# Battery_Power.net
KiCad netlist of a schematic drawn in Altium Designer
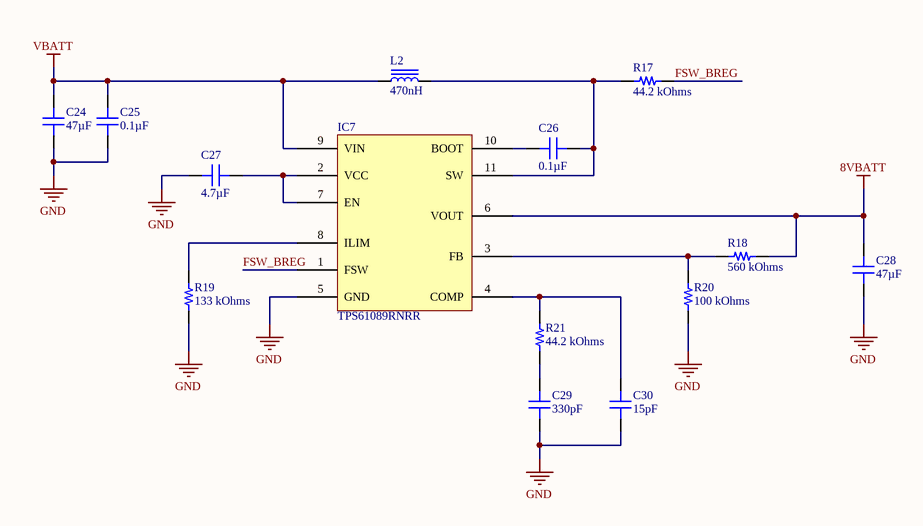
[diagram p0: Battery Power.SchDoc]

(export (version "E")
  (design (tool "Eeschema 10.0.6"))
  (components
    (comp (ref "C24")
      (value "47µF")
      (footprint "CAP 1210_3225 - 2.8MM")
      (description "CAP CER 47UF 10V X7R 1210")
      (fields (field (name "PART NUMBER") "LMK325B7476MM-PR") (field (name "MANUFACTURER") "Taiyo Yuden"))
      (libsource (lib "Celestial Altium Library - altium_library") (part "Capacitor"))
    )
    (comp (ref "C25")
      (value "0.1µF")
      (footprint "CAP 0201_0603")
      (description "CAP CER 0.1UF 16V X5R 0201")
      (fields
        (field (name "PART NUMBER") "GRM033R61C104ME84D")
        (field (name "MANUFACTURER") "Murata Electronics")
      )
      (libsource (lib "Celestial Altium Library - altium_library") (part "Capacitor"))
    )
    (comp (ref "C26")
      (value "0.1µF")
      (footprint "CAP 0201_0603")
      (description "CAP CER 0.1UF 16V X5R 0201")
      (fields
        (field (name "PART NUMBER") "GRM033R61C104ME84D")
        (field (name "MANUFACTURER") "Murata Electronics")
      )
      (libsource (lib "Celestial Altium Library - altium_library") (part "Capacitor"))
    )
    (comp (ref "C27")
      (value "4.7µF")
      (footprint "CAP 0402_1005")
      (description "CAP CER 4.7UF 10V X5R 0402")
      (fields
        (field (name "PART NUMBER") "CL05A475KP5NRNC")
        (field (name "MANUFACTURER") "Samsung Electro-Mechanics")
      )
      (libsource (lib "Celestial Altium Library - altium_library") (part "Capacitor"))
    )
    (comp (ref "C28")
      (value "47µF")
      (footprint "CAP 1210_3225 - 2.8MM")
      (description "CAP CER 47UF 16V X5R 1210")
      (fields (field (name "PART NUMBER") "C1210C476M4PACTU") (field (name "MANUFACTURER") "KEMET"))
      (libsource (lib "Celestial Altium Library - altium_library") (part "Capacitor"))
    )
    (comp (ref "C29")
      (value "330pF")
      (footprint "CAP 0201_0603")
      (description "CAP CER 330PF 25V X7R 0201")
      (fields
        (field (name "PART NUMBER") "CL03B331KA3NNNC")
        (field (name "MANUFACTURER") "Samsung Electro-Mechanics")
      )
      (libsource (lib "Celestial Altium Library - altium_library") (part "Capacitor"))
    )
    (comp (ref "C30")
      (value "15pF")
      (footprint "CAP 0201_0603")
      (description "CAP CER 15PF 25V C0G 0201")
      (fields
        (field (name "PART NUMBER") "CGA1A2C0G1E150J030BA")
        (field (name "MANUFACTURER") "TDK Corporation")
      )
      (libsource (lib "Celestial Altium Library - altium_library") (part "Capacitor"))
    )
    (comp (ref "IC7")
      (value "TPS61089RNRR")
      (footprint "TI VQFN-11 2.5x2.1 RNR")
      (description "IC REG BOOST ADJ 7A 11VQFN")
      (fields (field (name "MANUFACTURER") "Texas Instruments"))
      (libsource (lib "Celestial Altium Library - altium_library") (part "TI TPS61089"))
    )
    (comp (ref "L2")
      (value "470nH")
      (footprint "BOURNS SRP5030T")
      (description "FIXED IND 470NH 12A 7.4 MOHM SMD")
      (fields (field (name "PART NUMBER") "SRP5030T-R47M") (field (name "MANUFACTURER") "Bourns Inc."))
      (libsource (lib "Celestial Altium Library - altium_library") (part "Inductor"))
    )
    (comp (ref "R17")
      (value "44.2 kOhms")
      (footprint "RES 0201_0603")
      (description "RES SMD 44.2K OHM 1% 1/20W 0201")
      (fields
        (field (name "PART NUMBER") "ERJ-1GNF4422C")
        (field (name "MANUFACTURER") "Panasonic Electronic Components")
      )
      (libsource (lib "Celestial Altium Library - altium_library") (part "Resistor"))
    )
    (comp (ref "R18")
      (value "560 kOhms")
      (footprint "RES 0201_0603")
      (description "RES SMD 560K OHM 1% 1/20W 0201")
      (fields
        (field (name "PART NUMBER") "ERJ-1GNF5603C")
        (field (name "MANUFACTURER") "Panasonic Electronic Components")
      )
      (libsource (lib "Celestial Altium Library - altium_library") (part "Resistor"))
    )
    (comp (ref "R19")
      (value "133 kOhms")
      (footprint "RES 0201_0603")
      (description "RES SMD 133K OHM 1% 1/20W 0201")
      (fields
        (field (name "PART NUMBER") "ERJ-1GNF1333C")
        (field (name "MANUFACTURER") "Panasonic Electronic Components")
      )
      (libsource (lib "Celestial Altium Library - altium_library") (part "Resistor"))
    )
    (comp (ref "R20")
      (value "100 kOhms")
      (footprint "RES 0201_0603")
      (description "RES SMD 100K OHM 1% 1/20W 0201")
      (fields
        (field (name "PART NUMBER") "ERJ-1GNF1003C")
        (field (name "MANUFACTURER") "Panasonic Electronic Components")
      )
      (libsource (lib "Celestial Altium Library - altium_library") (part "Resistor"))
    )
    (comp (ref "R21")
      (value "44.2 kOhms")
      (footprint "RES 0201_0603")
      (description "RES SMD 44.2K OHM 1% 1/20W 0201")
      (fields
        (field (name "PART NUMBER") "ERJ-1GNF4422C")
        (field (name "MANUFACTURER") "Panasonic Electronic Components")
      )
      (libsource (lib "Celestial Altium Library - altium_library") (part "Resistor"))
    )
  )
  (nets
    (net (code "1") (name "/FSW_BREG") (class "Default")
      (node (ref "IC7") (pin "1") (pinfunction "FSW_1") (pintype "passive"))
      (node (ref "R17") (pin "2") (pinfunction "2_2") (pintype "passive"))
    )
    (net (code "2") (name "8VBATT") (class "Default")
      (node (ref "C28") (pin "2") (pinfunction "2_2") (pintype "passive"))
      (node (ref "IC7") (pin "6") (pinfunction "VOUT_6") (pintype "passive"))
      (node (ref "R18") (pin "1") (pinfunction "1_1") (pintype "passive"))
    )
    (net (code "3") (name "GND") (class "Default")
      (node (ref "C24") (pin "1") (pinfunction "1_1") (pintype "passive"))
      (node (ref "C25") (pin "1") (pinfunction "1_1") (pintype "passive"))
      (node (ref "C27") (pin "1") (pinfunction "1_1") (pintype "passive"))
      (node (ref "C28") (pin "1") (pinfunction "1_1") (pintype "passive"))
      (node (ref "C29") (pin "1") (pinfunction "1_1") (pintype "passive"))
      (node (ref "C30") (pin "1") (pinfunction "1_1") (pintype "passive"))
      (node (ref "IC7") (pin "5") (pinfunction "GND_5") (pintype "passive"))
      (node (ref "R19") (pin "1") (pinfunction "1_1") (pintype "passive"))
      (node (ref "R20") (pin "1") (pinfunction "1_1") (pintype "passive"))
    )
    (net (code "4") (name "Net-(C29-Pad2)") (class "Default")
      (node (ref "C29") (pin "2") (pinfunction "2_2") (pintype "passive"))
      (node (ref "R21") (pin "1") (pinfunction "1_1") (pintype "passive"))
    )
    (net (code "5") (name "Net-(IC7-BOOT)") (class "Default")
      (node (ref "C26") (pin "2") (pinfunction "2_2") (pintype "passive"))
      (node (ref "IC7") (pin "10") (pinfunction "BOOT_10") (pintype "passive"))
    )
    (net (code "6") (name "Net-(IC7-COMP)") (class "Default")
      (node (ref "C30") (pin "2") (pinfunction "2_2") (pintype "passive"))
      (node (ref "IC7") (pin "4") (pinfunction "COMP_4") (pintype "passive"))
      (node (ref "R21") (pin "2") (pinfunction "2_2") (pintype "passive"))
    )
    (net (code "7") (name "Net-(IC7-EN)") (class "Default")
      (node (ref "C27") (pin "2") (pinfunction "2_2") (pintype "passive"))
      (node (ref "IC7") (pin "2") (pinfunction "VCC_2") (pintype "passive"))
      (node (ref "IC7") (pin "7") (pinfunction "EN_7") (pintype "passive"))
    )
    (net (code "8") (name "Net-(IC7-FB)") (class "Default")
      (node (ref "IC7") (pin "3") (pinfunction "FB_3") (pintype "passive"))
      (node (ref "R18") (pin "2") (pinfunction "2_2") (pintype "passive"))
      (node (ref "R20") (pin "2") (pinfunction "2_2") (pintype "passive"))
    )
    (net (code "9") (name "Net-(IC7-ILIM)") (class "Default")
      (node (ref "IC7") (pin "8") (pinfunction "ILIM_8") (pintype "passive"))
      (node (ref "R19") (pin "2") (pinfunction "2_2") (pintype "passive"))
    )
    (net (code "10") (name "Net-(IC7-SW)") (class "Default")
      (node (ref "C26") (pin "1") (pinfunction "1_1") (pintype "passive"))
      (node (ref "IC7") (pin "11") (pinfunction "SW_11") (pintype "passive"))
      (node (ref "L2") (pin "2") (pinfunction "2_2") (pintype "passive"))
      (node (ref "R17") (pin "1") (pinfunction "1_1") (pintype "passive"))
    )
    (net (code "11") (name "VBATT") (class "Default")
      (node (ref "C24") (pin "2") (pinfunction "2_2") (pintype "passive"))
      (node (ref "C25") (pin "2") (pinfunction "2_2") (pintype "passive"))
      (node (ref "IC7") (pin "9") (pinfunction "VIN_9") (pintype "passive"))
      (node (ref "L2") (pin "1") (pinfunction "1_1") (pintype "passive"))
    )
  )
)
